# FPGA_IO_4.net
KiCad netlist of a schematic drawn in Altium Designer
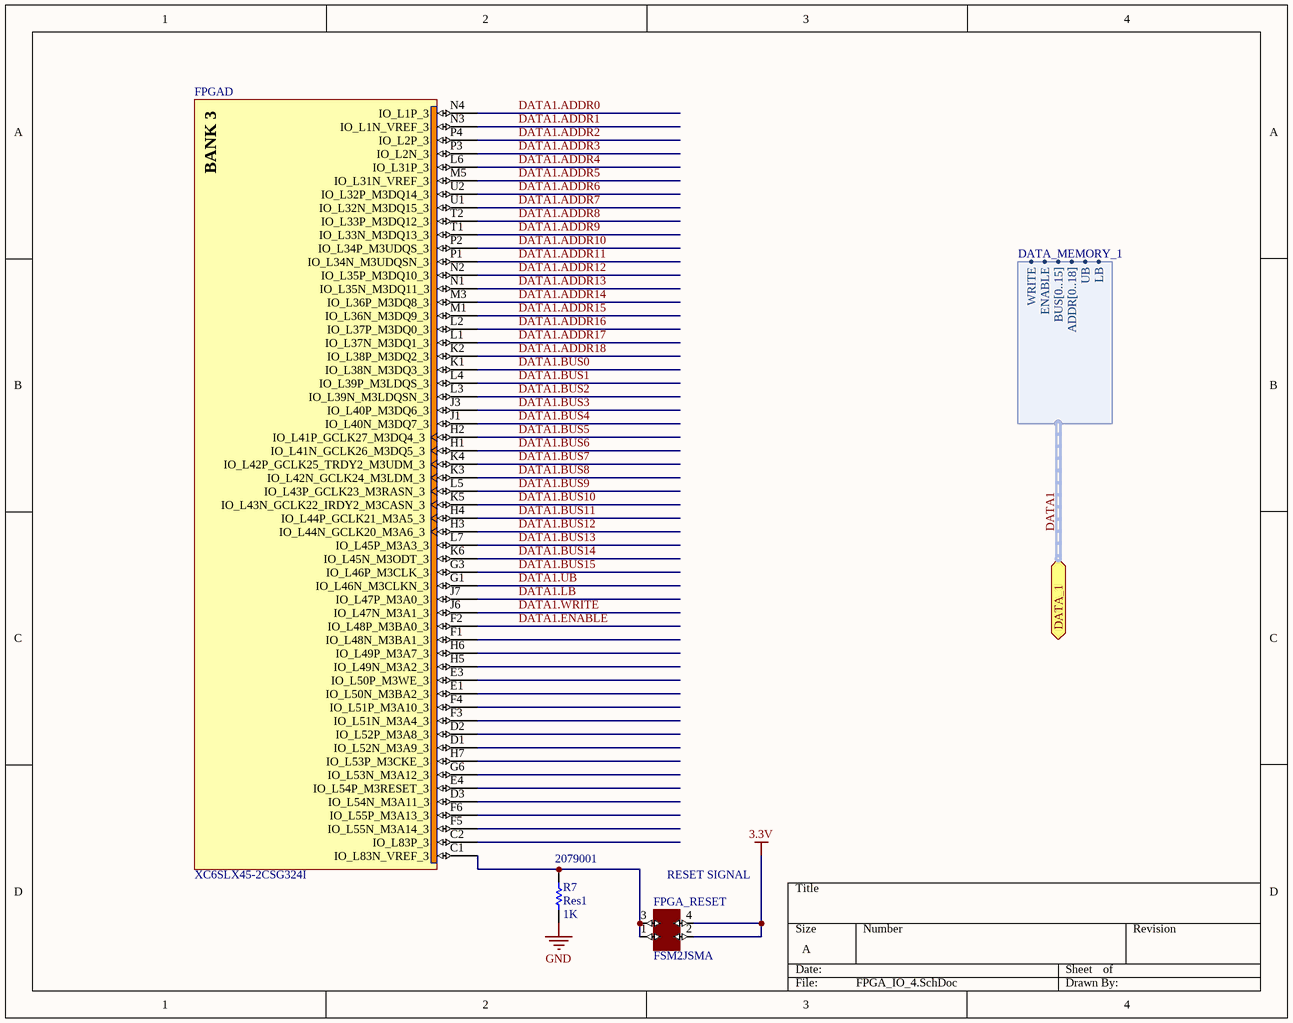
[diagram p0: FPGA_IO_4.SchDoc]

(export (version "E")
  (design (tool "Eeschema 10.0.6"))
  (components
    (comp (ref "FPGA")
      (value "XC6SLX45-2CSG324I")
      (footprint "CSG324")
      (libsource (lib "Altium Content Vault") (part "CMP-0067-00402-1"))
    )
    (comp (ref "FPGA_RESET")
      (value "FSM2JSMA")
      (footprint "button:Button")
      (libsource (lib "button") (part "switch-button"))
    )
    (comp (ref "R7")
      (value "Res1")
      (footprint "C1206")
      (description "Resistor")
      (fields
        (field (name "ALTIUM_VALUE") "1K")
        (field (name "SUPPLIER PART NUMBER 1") "2079001")
        (field (name "MANUFACTURER") "WELWYN")
        (field (name "MANUFACTURER PART NUMBER") "ASC1206-1K0FT5")
        (field (name "PUBLISHER") "Altium Limited")
      )
      (libsource (lib "Miscellaneous Devices") (part "Res1"))
    )
  )
  (nets
    (net (code "2") (name "/DATA1.ADDR0") (class "Default")
      (node (ref "FPGA") (pin "N4") (pinfunction "IO_L1P_3_N4") (pintype "bidirectional"))
    )
    (net (code "3") (name "/DATA1.ADDR1") (class "Default")
      (node (ref "FPGA") (pin "N3") (pinfunction "IO_L1N_VREF_3_N3") (pintype "bidirectional"))
    )
    (net (code "4") (name "/DATA1.ADDR2") (class "Default")
      (node (ref "FPGA") (pin "P4") (pinfunction "IO_L2P_3_P4") (pintype "bidirectional"))
    )
    (net (code "5") (name "/DATA1.ADDR3") (class "Default")
      (node (ref "FPGA") (pin "P3") (pinfunction "IO_L2N_3_P3") (pintype "bidirectional"))
    )
    (net (code "6") (name "/DATA1.ADDR4") (class "Default")
      (node (ref "FPGA") (pin "L6") (pinfunction "IO_L31P_3_L6") (pintype "bidirectional"))
    )
    (net (code "7") (name "/DATA1.ADDR5") (class "Default")
      (node (ref "FPGA") (pin "M5") (pinfunction "IO_L31N_VREF_3_M5") (pintype "bidirectional"))
    )
    (net (code "8") (name "/DATA1.ADDR6") (class "Default")
      (node (ref "FPGA") (pin "U2") (pinfunction "IO_L32P_M3DQ14_3_U2") (pintype "bidirectional"))
    )
    (net (code "9") (name "/DATA1.ADDR7") (class "Default")
      (node (ref "FPGA") (pin "U1") (pinfunction "IO_L32N_M3DQ15_3_U1") (pintype "bidirectional"))
    )
    (net (code "10") (name "/DATA1.ADDR8") (class "Default")
      (node (ref "FPGA") (pin "T2") (pinfunction "IO_L33P_M3DQ12_3_T2") (pintype "bidirectional"))
    )
    (net (code "11") (name "/DATA1.ADDR9") (class "Default")
      (node (ref "FPGA") (pin "T1") (pinfunction "IO_L33N_M3DQ13_3_T1") (pintype "bidirectional"))
    )
    (net (code "12") (name "/DATA1.ADDR10") (class "Default")
      (node (ref "FPGA") (pin "P2") (pinfunction "IO_L34P_M3UDQS_3_P2") (pintype "bidirectional"))
    )
    (net (code "13") (name "/DATA1.ADDR11") (class "Default")
      (node (ref "FPGA") (pin "P1") (pinfunction "IO_L34N_M3UDQSN_3_P1") (pintype "bidirectional"))
    )
    (net (code "14") (name "/DATA1.ADDR12") (class "Default")
      (node (ref "FPGA") (pin "N2") (pinfunction "IO_L35P_M3DQ10_3_N2") (pintype "bidirectional"))
    )
    (net (code "15") (name "/DATA1.ADDR13") (class "Default")
      (node (ref "FPGA") (pin "N1") (pinfunction "IO_L35N_M3DQ11_3_N1") (pintype "bidirectional"))
    )
    (net (code "16") (name "/DATA1.ADDR14") (class "Default")
      (node (ref "FPGA") (pin "M3") (pinfunction "IO_L36P_M3DQ8_3_M3") (pintype "bidirectional"))
    )
    (net (code "17") (name "/DATA1.ADDR15") (class "Default")
      (node (ref "FPGA") (pin "M1") (pinfunction "IO_L36N_M3DQ9_3_M1") (pintype "bidirectional"))
    )
    (net (code "18") (name "/DATA1.ADDR16") (class "Default")
      (node (ref "FPGA") (pin "L2") (pinfunction "IO_L37P_M3DQ0_3_L2") (pintype "bidirectional"))
    )
    (net (code "19") (name "/DATA1.ADDR17") (class "Default")
      (node (ref "FPGA") (pin "L1") (pinfunction "IO_L37N_M3DQ1_3_L1") (pintype "bidirectional"))
    )
    (net (code "20") (name "/DATA1.ADDR18") (class "Default")
      (node (ref "FPGA") (pin "K2") (pinfunction "IO_L38P_M3DQ2_3_K2") (pintype "bidirectional"))
    )
    (net (code "21") (name "/DATA1.BUS0") (class "Default")
      (node (ref "FPGA") (pin "K1") (pinfunction "IO_L38N_M3DQ3_3_K1") (pintype "bidirectional"))
    )
    (net (code "22") (name "/DATA1.BUS1") (class "Default")
      (node (ref "FPGA") (pin "L4") (pinfunction "IO_L39P_M3LDQS_3_L4") (pintype "bidirectional"))
    )
    (net (code "23") (name "/DATA1.BUS2") (class "Default")
      (node (ref "FPGA") (pin "L3") (pinfunction "IO_L39N_M3LDQSN_3_L3") (pintype "bidirectional"))
    )
    (net (code "24") (name "/DATA1.BUS3") (class "Default")
      (node (ref "FPGA") (pin "J3") (pinfunction "IO_L40P_M3DQ6_3_J3") (pintype "bidirectional"))
    )
    (net (code "25") (name "/DATA1.BUS4") (class "Default")
      (node (ref "FPGA") (pin "J1") (pinfunction "IO_L40N_M3DQ7_3_J1") (pintype "bidirectional"))
    )
    (net (code "26") (name "/DATA1.BUS5") (class "Default")
      (node (ref "FPGA") (pin "H2") (pinfunction "IO_L41P_GCLK27_M3DQ4_3_H2") (pintype "bidirectional"))
    )
    (net (code "27") (name "/DATA1.BUS6") (class "Default")
      (node (ref "FPGA") (pin "H1") (pinfunction "IO_L41N_GCLK26_M3DQ5_3_H1") (pintype "bidirectional"))
    )
    (net (code "28") (name "/DATA1.BUS7") (class "Default")
      (node (ref "FPGA") (pin "K4") (pinfunction "IO_L42P_GCLK25_TRDY2_M3UDM_3_K4") (pintype "bidirectional"))
    )
    (net (code "29") (name "/DATA1.BUS8") (class "Default")
      (node (ref "FPGA") (pin "K3") (pinfunction "IO_L42N_GCLK24_M3LDM_3_K3") (pintype "bidirectional"))
    )
    (net (code "30") (name "/DATA1.BUS9") (class "Default")
      (node (ref "FPGA") (pin "L5") (pinfunction "IO_L43P_GCLK23_M3RASN_3_L5") (pintype "bidirectional"))
    )
    (net (code "31") (name "/DATA1.BUS10") (class "Default")
      (node (ref "FPGA") (pin "K5") (pinfunction "IO_L43N_GCLK22_IRDY2_M3CASN_3_K5") (pintype "bidirectional"))
    )
    (net (code "32") (name "/DATA1.BUS11") (class "Default")
      (node (ref "FPGA") (pin "H4") (pinfunction "IO_L44P_GCLK21_M3A5_3_H4") (pintype "bidirectional"))
    )
    (net (code "33") (name "/DATA1.BUS12") (class "Default")
      (node (ref "FPGA") (pin "H3") (pinfunction "IO_L44N_GCLK20_M3A6_3_H3") (pintype "bidirectional"))
    )
    (net (code "34") (name "/DATA1.BUS13") (class "Default")
      (node (ref "FPGA") (pin "L7") (pinfunction "IO_L45P_M3A3_3_L7") (pintype "bidirectional"))
    )
    (net (code "35") (name "/DATA1.BUS14") (class "Default")
      (node (ref "FPGA") (pin "K6") (pinfunction "IO_L45N_M3ODT_3_K6") (pintype "bidirectional"))
    )
    (net (code "36") (name "/DATA1.BUS15") (class "Default")
      (node (ref "FPGA") (pin "G3") (pinfunction "IO_L46P_M3CLK_3_G3") (pintype "bidirectional"))
    )
    (net (code "37") (name "/DATA1.ENABLE") (class "Default")
      (node (ref "FPGA") (pin "F2") (pinfunction "IO_L48P_M3BA0_3_F2") (pintype "bidirectional"))
    )
    (net (code "38") (name "/DATA1.LB") (class "Default")
      (node (ref "FPGA") (pin "J7") (pinfunction "IO_L47P_M3A0_3_J7") (pintype "bidirectional"))
    )
    (net (code "39") (name "/DATA1.UB") (class "Default")
      (node (ref "FPGA") (pin "G1") (pinfunction "IO_L46N_M3CLKN_3_G1") (pintype "bidirectional"))
    )
    (net (code "40") (name "/DATA1.WRITE") (class "Default")
      (node (ref "FPGA") (pin "J6") (pinfunction "IO_L47N_M3A1_3_J6") (pintype "bidirectional"))
    )
    (net (code "42") (name "3.3V") (class "Default")
      (node (ref "FPGA_RESET") (pin "2") (pinfunction "2_2") (pintype "bidirectional"))
      (node (ref "FPGA_RESET") (pin "4") (pinfunction "4_4") (pintype "bidirectional"))
    )
    (net (code "43") (name "GND") (class "Default")
      (node (ref "R7") (pin "2") (pinfunction "2_2") (pintype "passive"))
    )
    (net (code "44") (name "Net-(FPGAD-IO_L83N_VREF_3)") (class "Default")
      (node (ref "FPGA") (pin "C1") (pinfunction "IO_L83N_VREF_3_C1") (pintype "bidirectional"))
      (node (ref "FPGA_RESET") (pin "1") (pinfunction "1_1") (pintype "bidirectional"))
      (node (ref "FPGA_RESET") (pin "3") (pinfunction "3_3") (pintype "bidirectional"))
      (node (ref "R7") (pin "1") (pinfunction "1_1") (pintype "passive"))
    )
    (net (code "45") (name "unconnected-(FPGAD-IO_L48N_M3BA1_3-PadF1)") (class "Default")
      (node (ref "FPGA") (pin "F1") (pinfunction "IO_L48N_M3BA1_3_F1") (pintype "bidirectional"))
    )
    (net (code "46") (name "unconnected-(FPGAD-IO_L49N_M3A2_3-PadH5)") (class "Default")
      (node (ref "FPGA") (pin "H5") (pinfunction "IO_L49N_M3A2_3_H5") (pintype "bidirectional"))
    )
    (net (code "47") (name "unconnected-(FPGAD-IO_L49P_M3A7_3-PadH6)") (class "Default")
      (node (ref "FPGA") (pin "H6") (pinfunction "IO_L49P_M3A7_3_H6") (pintype "bidirectional"))
    )
    (net (code "48") (name "unconnected-(FPGAD-IO_L50N_M3BA2_3-PadE1)") (class "Default")
      (node (ref "FPGA") (pin "E1") (pinfunction "IO_L50N_M3BA2_3_E1") (pintype "bidirectional"))
    )
    (net (code "49") (name "unconnected-(FPGAD-IO_L50P_M3WE_3-PadE3)") (class "Default")
      (node (ref "FPGA") (pin "E3") (pinfunction "IO_L50P_M3WE_3_E3") (pintype "bidirectional"))
    )
    (net (code "50") (name "unconnected-(FPGAD-IO_L51N_M3A4_3-PadF3)") (class "Default")
      (node (ref "FPGA") (pin "F3") (pinfunction "IO_L51N_M3A4_3_F3") (pintype "bidirectional"))
    )
    (net (code "51") (name "unconnected-(FPGAD-IO_L51P_M3A10_3-PadF4)") (class "Default")
      (node (ref "FPGA") (pin "F4") (pinfunction "IO_L51P_M3A10_3_F4") (pintype "bidirectional"))
    )
    (net (code "52") (name "unconnected-(FPGAD-IO_L52N_M3A9_3-PadD1)") (class "Default")
      (node (ref "FPGA") (pin "D1") (pinfunction "IO_L52N_M3A9_3_D1") (pintype "bidirectional"))
    )
    (net (code "53") (name "unconnected-(FPGAD-IO_L52P_M3A8_3-PadD2)") (class "Default")
      (node (ref "FPGA") (pin "D2") (pinfunction "IO_L52P_M3A8_3_D2") (pintype "bidirectional"))
    )
    (net (code "54") (name "unconnected-(FPGAD-IO_L53N_M3A12_3-PadG6)") (class "Default")
      (node (ref "FPGA") (pin "G6") (pinfunction "IO_L53N_M3A12_3_G6") (pintype "bidirectional"))
    )
    (net (code "55") (name "unconnected-(FPGAD-IO_L53P_M3CKE_3-PadH7)") (class "Default")
      (node (ref "FPGA") (pin "H7") (pinfunction "IO_L53P_M3CKE_3_H7") (pintype "bidirectional"))
    )
    (net (code "56") (name "unconnected-(FPGAD-IO_L54N_M3A11_3-PadD3)") (class "Default")
      (node (ref "FPGA") (pin "D3") (pinfunction "IO_L54N_M3A11_3_D3") (pintype "bidirectional"))
    )
    (net (code "57") (name "unconnected-(FPGAD-IO_L54P_M3RESET_3-PadE4)") (class "Default")
      (node (ref "FPGA") (pin "E4") (pinfunction "IO_L54P_M3RESET_3_E4") (pintype "bidirectional"))
    )
    (net (code "58") (name "unconnected-(FPGAD-IO_L55N_M3A14_3-PadF5)") (class "Default")
      (node (ref "FPGA") (pin "F5") (pinfunction "IO_L55N_M3A14_3_F5") (pintype "bidirectional"))
    )
    (net (code "59") (name "unconnected-(FPGAD-IO_L55P_M3A13_3-PadF6)") (class "Default")
      (node (ref "FPGA") (pin "F6") (pinfunction "IO_L55P_M3A13_3_F6") (pintype "bidirectional"))
    )
    (net (code "60") (name "unconnected-(FPGAD-IO_L83P_3-PadC2)") (class "Default")
      (node (ref "FPGA") (pin "C2") (pinfunction "IO_L83P_3_C2") (pintype "bidirectional"))
    )
  )
)
